# M_D_ext_power_old.net
KiCad netlist of a schematic drawn in EAGLE
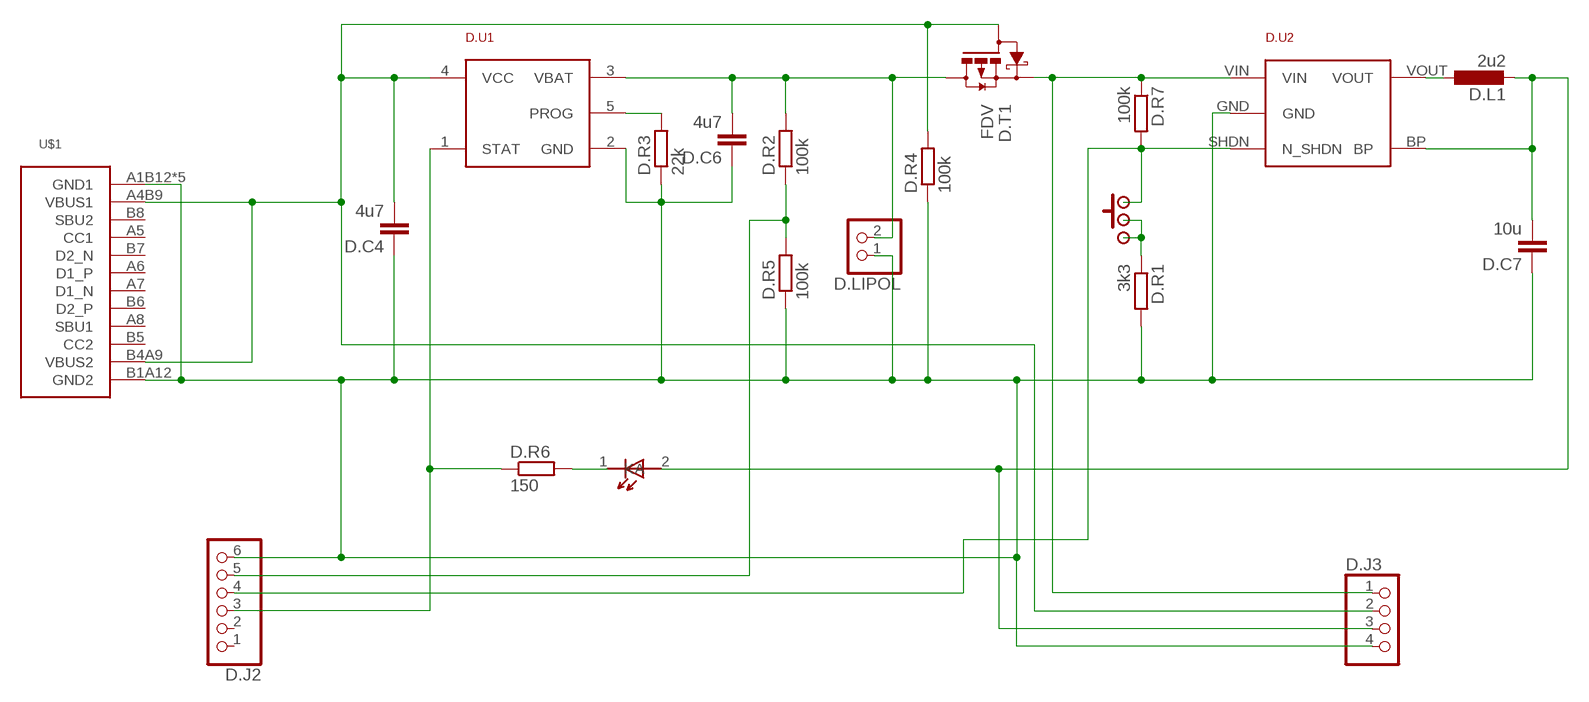
[diagram p0: schematic, sheet 1]

(export (version "E")
  (design (tool "Eeschema 10.0.6"))
  (components
    (comp (ref "D.C4")
      (value "4u7")
      (footprint "eagle-import:C0603")
      (libsource (lib "eagle-import") (part "C-EUC0603"))
    )
    (comp (ref "D.C6")
      (value "4u7")
      (footprint "eagle-import:C0603")
      (libsource (lib "eagle-import") (part "C-EUC0603"))
    )
    (comp (ref "D.C7")
      (value "10u")
      (footprint "eagle-import:C0603")
      (libsource (lib "eagle-import") (part "C-EUC0603"))
    )
    (comp (ref "D.D1")
      (value "LED_1.8")
      (footprint "eagle-import:LED_1.8")
      (libsource (lib "eagle-import") (part "LED_1.8"))
    )
    (comp (ref "D.J2")
      (value "PINHD-1X6")
      (footprint "eagle-import:1X06")
      (libsource (lib "eagle-import") (part "PINHD-1X6"))
    )
    (comp (ref "D.J3")
      (value "PINHD-1X4")
      (footprint "eagle-import:1X04")
      (libsource (lib "eagle-import") (part "PINHD-1X4"))
    )
    (comp (ref "D.L1")
      (value "2u2")
      (footprint "eagle-import:L3230M")
      (libsource (lib "eagle-import") (part "L-EUL3230M"))
    )
    (comp (ref "D.LIPOL")
      (value "PINHD-1X2")
      (footprint "eagle-import:1X02")
      (libsource (lib "eagle-import") (part "PINHD-1X2"))
    )
    (comp (ref "D.ON/OFF/RESET")
      (value "SWITCH")
      (footprint "eagle-import:SWITCH")
      (libsource (lib "eagle-import") (part "SWITCH"))
    )
    (comp (ref "D.R1")
      (value "3k3")
      (footprint "eagle-import:R0603")
      (libsource (lib "eagle-import") (part "R-EU_R0603"))
    )
    (comp (ref "D.R2")
      (value "100k")
      (footprint "eagle-import:R0603")
      (libsource (lib "eagle-import") (part "R-EU_R0603"))
    )
    (comp (ref "D.R3")
      (value "22k")
      (footprint "eagle-import:R0603")
      (libsource (lib "eagle-import") (part "R-EU_R0603"))
    )
    (comp (ref "D.R4")
      (value "100k")
      (footprint "eagle-import:R0603")
      (libsource (lib "eagle-import") (part "R-EU_R0603"))
    )
    (comp (ref "D.R5")
      (value "100k")
      (footprint "eagle-import:R0603")
      (libsource (lib "eagle-import") (part "R-EU_R0603"))
    )
    (comp (ref "D.R6")
      (value "150")
      (footprint "eagle-import:R0603")
      (libsource (lib "eagle-import") (part "R-EU_R0603"))
    )
    (comp (ref "D.R7")
      (value "100k")
      (footprint "eagle-import:R0603")
      (libsource (lib "eagle-import") (part "R-EU_R0603"))
    )
    (comp (ref "D.T1")
      (value "FDV")
      (footprint "eagle-import:SOT23")
      (libsource (lib "eagle-import") (part "P-MOSFET-FDV304P"))
    )
    (comp (ref "D.U1")
      (value "MCP")
      (footprint "eagle-import:SOT23-5")
      (libsource (lib "eagle-import") (part "MCP73831"))
    )
    (comp (ref "D.U2")
      (value "TC")
      (footprint "eagle-import:SOT32-5")
      (libsource (lib "eagle-import") (part "STABILISER_APE8865"))
    )
    (comp (ref "U$1")
      (value "USB-C")
      (footprint "eagle-import:USB-C")
      (libsource (lib "eagle-import") (part "USB-C"))
    )
  )
  (nets
    (net (code "1") (name "Net-(D.D1-A)") (class "Default")
      (node (ref "D.C7") (pin "2") (pinfunction "2_2") (pintype "passive"))
      (node (ref "D.D1") (pin "2") (pinfunction "A_2") (pintype "bidirectional"))
      (node (ref "D.J3") (pin "3") (pinfunction "3_3") (pintype "passive"))
      (node (ref "D.L1") (pin "2") (pinfunction "2_2") (pintype "passive"))
      (node (ref "D.U2") (pin "BP") (pinfunction "BP_BP") (pintype "bidirectional"))
    )
    (net (code "2") (name "Net-(D.D1-K)") (class "Default")
      (node (ref "D.D1") (pin "1") (pinfunction "K_1") (pintype "bidirectional"))
      (node (ref "D.R6") (pin "2") (pinfunction "2_2") (pintype "passive"))
    )
    (net (code "3") (name "Net-(D.J2-Pad5)") (class "Default")
      (node (ref "D.J2") (pin "5") (pinfunction "5_5") (pintype "passive"))
      (node (ref "D.R2") (pin "1") (pinfunction "1_1") (pintype "passive"))
      (node (ref "D.R5") (pin "2") (pinfunction "2_2") (pintype "passive"))
    )
    (net (code "4") (name "Net-(D.J3-Pad1)") (class "Default")
      (node (ref "D.J3") (pin "1") (pinfunction "1_1") (pintype "passive"))
      (node (ref "D.R7") (pin "1") (pinfunction "1_1") (pintype "passive"))
      (node (ref "D.T1") (pin "S") (pinfunction "S_S") (pintype "passive"))
      (node (ref "D.U2") (pin "VIN") (pinfunction "VIN_VIN") (pintype "bidirectional"))
    )
    (net (code "5") (name "Net-(D.L1-Pad1)") (class "Default")
      (node (ref "D.L1") (pin "1") (pinfunction "1_1") (pintype "passive"))
      (node (ref "D.U2") (pin "VOUT") (pinfunction "VOUT_VOUT") (pintype "bidirectional"))
    )
    (net (code "6") (name "Net-(D.ON/OFF/RESET-P$3-PadP$5)") (class "Default")
      (node (ref "D.ON/OFF/RESET") (pin "P$2") (pinfunction "P$2_P$2") (pintype "bidirectional"))
      (node (ref "D.ON/OFF/RESET") (pin "P$3") (pinfunction "P$3_P$3") (pintype "bidirectional"))
      (node (ref "D.ON/OFF/RESET") (pin "P$5") (pinfunction "P$3_P$5") (pintype "bidirectional"))
      (node (ref "D.R1") (pin "1") (pinfunction "1_1") (pintype "passive"))
    )
    (net (code "7") (name "Net-(D.U1-GND)") (class "Default")
      (node (ref "D.C4") (pin "1") (pinfunction "1_1") (pintype "passive"))
      (node (ref "D.C6") (pin "1") (pinfunction "1_1") (pintype "passive"))
      (node (ref "D.C7") (pin "1") (pinfunction "1_1") (pintype "passive"))
      (node (ref "D.J2") (pin "6") (pinfunction "6_6") (pintype "passive"))
      (node (ref "D.J3") (pin "4") (pinfunction "4_4") (pintype "passive"))
      (node (ref "D.LIPOL") (pin "1") (pinfunction "1_1") (pintype "passive"))
      (node (ref "D.R1") (pin "2") (pinfunction "2_2") (pintype "passive"))
      (node (ref "D.R3") (pin "1") (pinfunction "1_1") (pintype "passive"))
      (node (ref "D.R4") (pin "1") (pinfunction "1_1") (pintype "passive"))
      (node (ref "D.R5") (pin "1") (pinfunction "1_1") (pintype "passive"))
      (node (ref "D.U1") (pin "2") (pinfunction "GND_2") (pintype "bidirectional"))
      (node (ref "D.U2") (pin "GND") (pinfunction "GND_GND") (pintype "bidirectional"))
      (node (ref "U$1") (pin "A1B12") (pinfunction "GND1_A1B12") (pintype "bidirectional"))
      (node (ref "U$1") (pin "B1A12") (pinfunction "GND2_B1A12") (pintype "bidirectional"))
      (node (ref "U$1") (pin "SH1") (pinfunction "GND1_SH1") (pintype "bidirectional"))
      (node (ref "U$1") (pin "SH2") (pinfunction "GND1_SH2") (pintype "bidirectional"))
      (node (ref "U$1") (pin "SH3") (pinfunction "GND1_SH3") (pintype "bidirectional"))
      (node (ref "U$1") (pin "SH4") (pinfunction "GND1_SH4") (pintype "bidirectional"))
    )
    (net (code "8") (name "Net-(D.U1-PROG)") (class "Default")
      (node (ref "D.R3") (pin "2") (pinfunction "2_2") (pintype "passive"))
      (node (ref "D.U1") (pin "5") (pinfunction "PROG_5") (pintype "bidirectional"))
    )
    (net (code "9") (name "Net-(D.U1-STAT)") (class "Default")
      (node (ref "D.J2") (pin "3") (pinfunction "3_3") (pintype "passive"))
      (node (ref "D.R6") (pin "1") (pinfunction "1_1") (pintype "passive"))
      (node (ref "D.U1") (pin "1") (pinfunction "STAT_1") (pintype "bidirectional"))
    )
    (net (code "10") (name "Net-(D.U1-VBAT)") (class "Default")
      (node (ref "D.C6") (pin "2") (pinfunction "2_2") (pintype "passive"))
      (node (ref "D.LIPOL") (pin "2") (pinfunction "2_2") (pintype "passive"))
      (node (ref "D.R2") (pin "2") (pinfunction "2_2") (pintype "passive"))
      (node (ref "D.T1") (pin "D") (pinfunction "D_D") (pintype "passive"))
      (node (ref "D.U1") (pin "3") (pinfunction "VBAT_3") (pintype "bidirectional"))
    )
    (net (code "11") (name "Net-(D.U1-VCC)") (class "Default")
      (node (ref "D.C4") (pin "2") (pinfunction "2_2") (pintype "passive"))
      (node (ref "D.J3") (pin "2") (pinfunction "2_2") (pintype "passive"))
      (node (ref "D.R4") (pin "2") (pinfunction "2_2") (pintype "passive"))
      (node (ref "D.T1") (pin "G") (pinfunction "G_G") (pintype "passive"))
      (node (ref "D.U1") (pin "4") (pinfunction "VCC_4") (pintype "bidirectional"))
      (node (ref "U$1") (pin "A4B9") (pinfunction "VBUS1_A4B9") (pintype "bidirectional"))
      (node (ref "U$1") (pin "B4A9") (pinfunction "VBUS2_B4A9") (pintype "bidirectional"))
    )
    (net (code "12") (name "Net-(D.U2-N_SHDN)") (class "Default")
      (node (ref "D.J2") (pin "4") (pinfunction "4_4") (pintype "passive"))
      (node (ref "D.ON/OFF/RESET") (pin "P$1") (pinfunction "P$1_P$1") (pintype "bidirectional"))
      (node (ref "D.ON/OFF/RESET") (pin "P$4") (pinfunction "P$1_P$4") (pintype "bidirectional"))
      (node (ref "D.R7") (pin "2") (pinfunction "2_2") (pintype "passive"))
      (node (ref "D.U2") (pin "SHDN") (pinfunction "N_SHDN_SHDN") (pintype "bidirectional"))
    )
    (net (code "13") (name "unconnected-(D.J2-Pad1)") (class "Default")
      (node (ref "D.J2") (pin "1") (pinfunction "1_1") (pintype "passive"))
    )
    (net (code "14") (name "unconnected-(D.J2-Pad2)") (class "Default")
      (node (ref "D.J2") (pin "2") (pinfunction "2_2") (pintype "passive"))
    )
    (net (code "15") (name "unconnected-(U$1-CC1-PadA5)") (class "Default")
      (node (ref "U$1") (pin "A5") (pinfunction "CC1_A5") (pintype "bidirectional"))
    )
    (net (code "16") (name "unconnected-(U$1-CC2-PadB5)") (class "Default")
      (node (ref "U$1") (pin "B5") (pinfunction "CC2_B5") (pintype "bidirectional"))
    )
    (net (code "17") (name "unconnected-(U$1-D1_N-PadA7)") (class "Default")
      (node (ref "U$1") (pin "A7") (pinfunction "D1_N_A7") (pintype "bidirectional"))
    )
    (net (code "18") (name "unconnected-(U$1-D1_P-PadA6)") (class "Default")
      (node (ref "U$1") (pin "A6") (pinfunction "D1_P_A6") (pintype "bidirectional"))
    )
    (net (code "19") (name "unconnected-(U$1-D2_N-PadB7)") (class "Default")
      (node (ref "U$1") (pin "B7") (pinfunction "D2_N_B7") (pintype "bidirectional"))
    )
    (net (code "20") (name "unconnected-(U$1-D2_P-PadB6)") (class "Default")
      (node (ref "U$1") (pin "B6") (pinfunction "D2_P_B6") (pintype "bidirectional"))
    )
    (net (code "21") (name "unconnected-(U$1-SBU1-PadA8)") (class "Default")
      (node (ref "U$1") (pin "A8") (pinfunction "SBU1_A8") (pintype "bidirectional"))
    )
    (net (code "22") (name "unconnected-(U$1-SBU2-PadB8)") (class "Default")
      (node (ref "U$1") (pin "B8") (pinfunction "SBU2_B8") (pintype "bidirectional"))
    )
  )
)
